# RemoteControl-v1.net
KiCad netlist of a schematic drawn in EAGLE
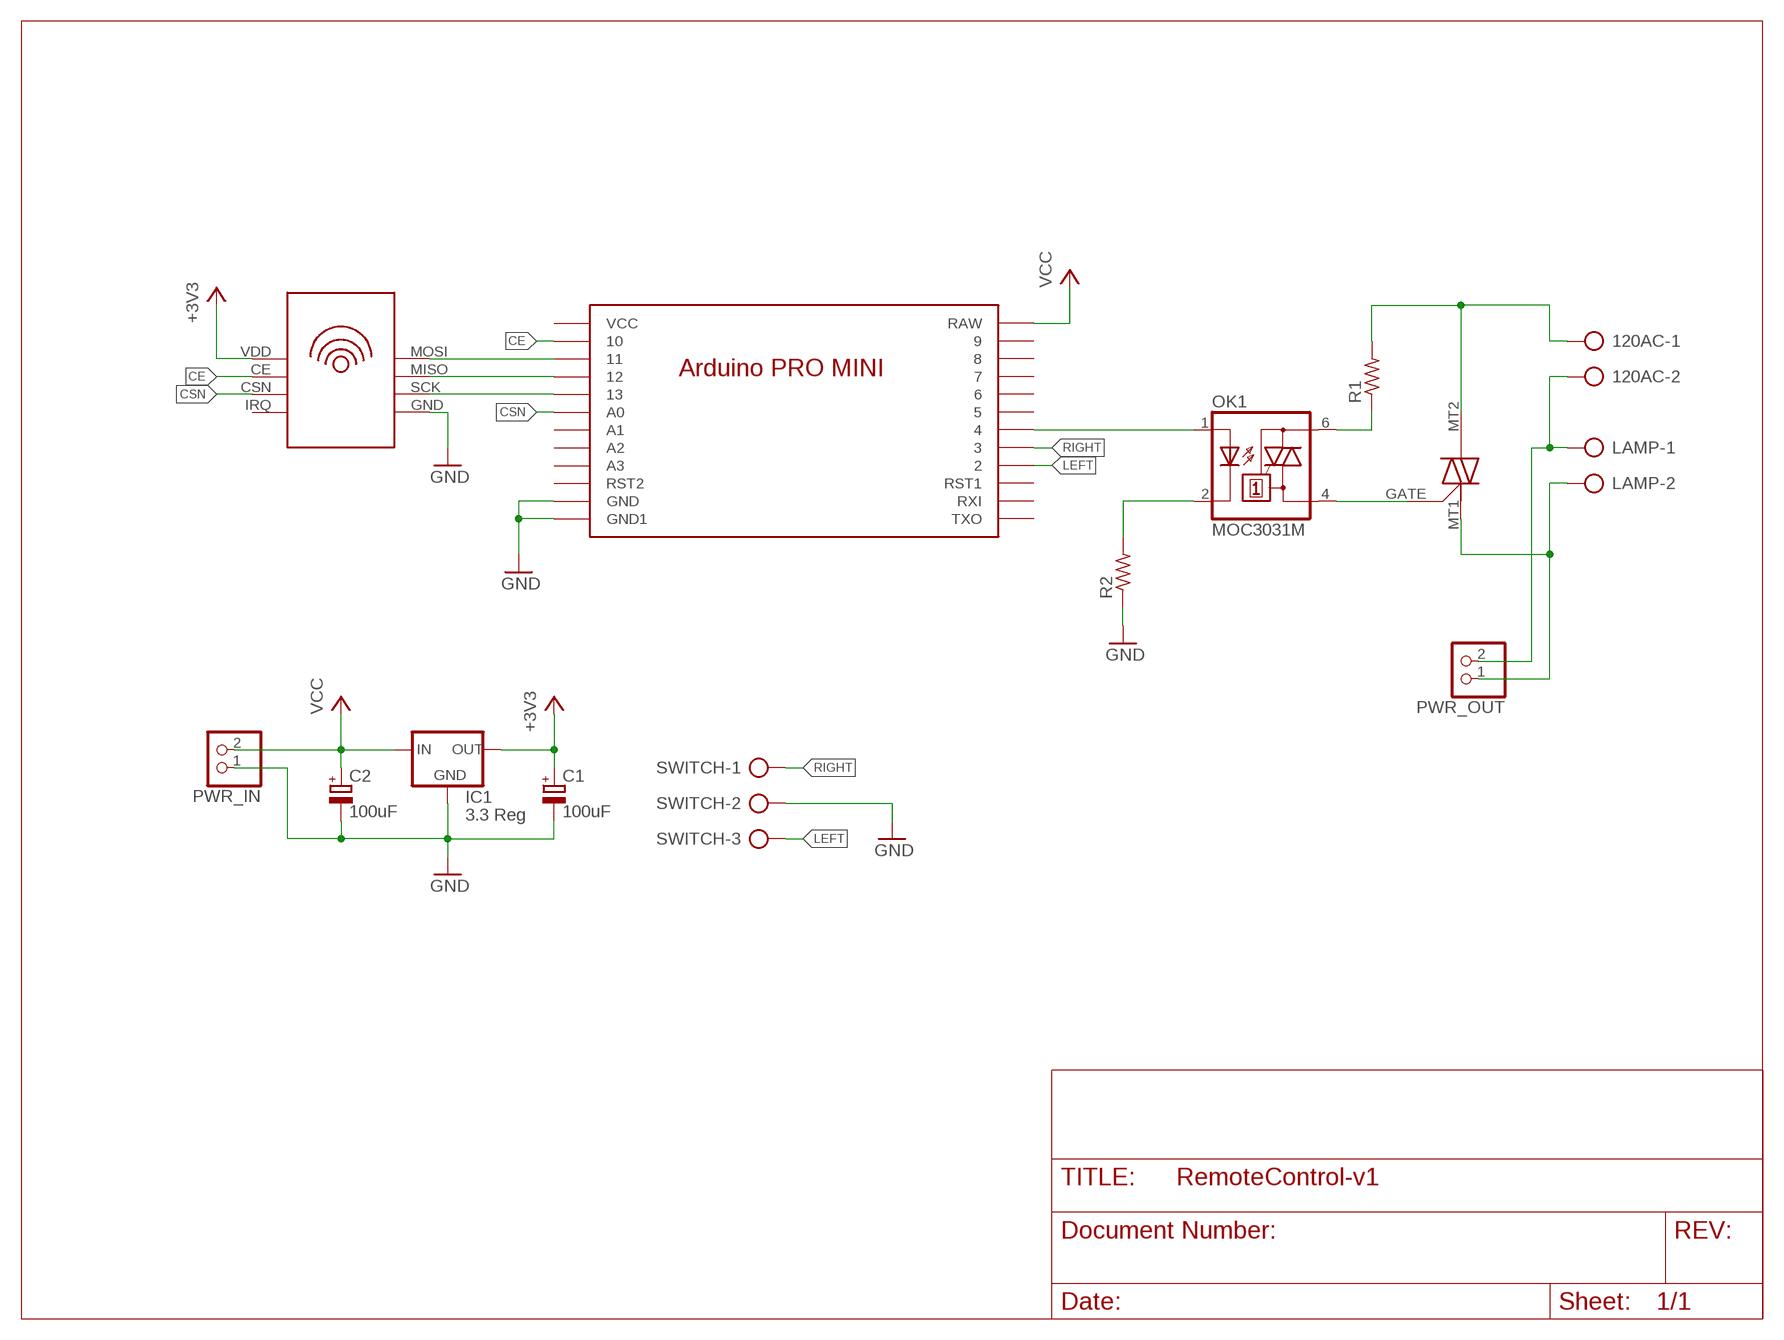
[diagram p0: schematic, sheet 1]

(export (version "E")
  (design (tool "Eeschema 10.0.6"))
  (components
    (comp (ref "120AC")
      (value "AK300/2")
      (footprint "eagle-import:AK300_2")
      (libsource (lib "eagle-import") (part "AK300/2"))
    )
    (comp (ref "C1")
      (value "100uF")
      (footprint "eagle-import:E2,5-5")
      (libsource (lib "eagle-import") (part "CPOL-EUE2.5-5"))
    )
    (comp (ref "C2")
      (value "100uF")
      (footprint "eagle-import:E2,5-5")
      (libsource (lib "eagle-import") (part "CPOL-EUE2.5-5"))
    )
    (comp (ref "IC1")
      (value "3.3 Reg")
      (footprint "eagle-import:78LXX")
      (libsource (lib "eagle-import") (part "78LXX"))
    )
    (comp (ref "LAMP")
      (value "AK300/2")
      (footprint "eagle-import:AK300_2")
      (libsource (lib "eagle-import") (part "AK300/2"))
    )
    (comp (ref "NRF24L01")
      (value "NRF24L01")
      (footprint "eagle-import:NRF24L01")
      (libsource (lib "eagle-import") (part "NRF24L01"))
    )
    (comp (ref "OK1")
      (value "MOC3031M")
      (footprint "eagle-import:DIL06")
      (fields (field (name "MF") "FAIRCHILD SEMICONDUCTOR"))
      (libsource (lib "eagle-import") (part "MOC3031M"))
    )
    (comp (ref "PWR_IN")
      (value "PINHD-1X2")
      (footprint "eagle-import:1X02")
      (libsource (lib "eagle-import") (part "PINHD-1X2"))
    )
    (comp (ref "PWR_OUT")
      (value "PINHD-1X2")
      (footprint "eagle-import:1X02")
      (libsource (lib "eagle-import") (part "PINHD-1X2"))
    )
    (comp (ref "R1")
      (value "R-US_0204/7")
      (footprint "eagle-import:0204_7")
      (libsource (lib "eagle-import") (part "R-US_0204/7"))
    )
    (comp (ref "R2")
      (value "R-US_0204/7")
      (footprint "eagle-import:0204_7")
      (libsource (lib "eagle-import") (part "R-US_0204/7"))
    )
    (comp (ref "SWITCH")
      (value "AK300/3")
      (footprint "eagle-import:AK300_3")
      (libsource (lib "eagle-import") (part "AK300/3"))
    )
    (comp (ref "U$1")
      (value "NANO")
      (footprint "eagle-import:NANO")
      (libsource (lib "eagle-import") (part "NANO"))
    )
    (comp (ref "U$2")
      (value "MAC12")
      (footprint "eagle-import:MAC12")
      (libsource (lib "eagle-import") (part "MAC12"))
    )
  )
  (nets
    (net (code "1") (name "+3V3") (class "Default")
      (node (ref "C1") (pin "+") (pinfunction "+_+") (pintype "passive"))
      (node (ref "IC1") (pin "OUT") (pinfunction "OUT_OUT") (pintype "passive"))
      (node (ref "NRF24L01") (pin "VDD") (pinfunction "VDD_VDD") (pintype "bidirectional"))
    )
    (net (code "2") (name "CE") (class "Default")
      (node (ref "NRF24L01") (pin "CE") (pinfunction "CE_CE") (pintype "bidirectional"))
      (node (ref "U$1") (pin "10") (pinfunction "10_10") (pintype "bidirectional"))
    )
    (net (code "3") (name "CSN") (class "Default")
      (node (ref "NRF24L01") (pin "CSN") (pinfunction "CSN_CSN") (pintype "bidirectional"))
      (node (ref "U$1") (pin "A0") (pinfunction "A0_A0") (pintype "bidirectional"))
    )
    (net (code "4") (name "GND") (class "Default")
      (node (ref "C1") (pin "-") (pinfunction "-_-") (pintype "passive"))
      (node (ref "C2") (pin "-") (pinfunction "-_-") (pintype "passive"))
      (node (ref "IC1") (pin "GND") (pinfunction "GND_GND") (pintype "input"))
      (node (ref "NRF24L01") (pin "GND") (pinfunction "GND_GND") (pintype "bidirectional"))
      (node (ref "PWR_IN") (pin "1") (pinfunction "1_1") (pintype "passive"))
      (node (ref "R2") (pin "1") (pinfunction "1_1") (pintype "passive"))
      (node (ref "SWITCH") (pin "2") (pinfunction "KL_2") (pintype "passive"))
      (node (ref "U$1") (pin "GND1") (pinfunction "GND_GND1") (pintype "bidirectional"))
      (node (ref "U$1") (pin "GND2") (pinfunction "GND1_GND2") (pintype "power_in"))
    )
    (net (code "5") (name "LEFT") (class "Default")
      (node (ref "SWITCH") (pin "3") (pinfunction "KL_3") (pintype "passive"))
      (node (ref "U$1") (pin "2") (pinfunction "2_2") (pintype "bidirectional"))
    )
    (net (code "6") (name "Net-(120ACA-KL)") (class "Default")
      (node (ref "120AC") (pin "1") (pinfunction "KL_1") (pintype "passive"))
      (node (ref "R1") (pin "2") (pinfunction "2_2") (pintype "passive"))
      (node (ref "U$2") (pin "MT2") (pinfunction "MT2_MT2") (pintype "bidirectional"))
    )
    (net (code "7") (name "Net-(120ACB-KL)") (class "Default")
      (node (ref "120AC") (pin "2") (pinfunction "KL_2") (pintype "passive"))
      (node (ref "LAMP") (pin "1") (pinfunction "KL_1") (pintype "passive"))
      (node (ref "PWR_OUT") (pin "2") (pinfunction "2_2") (pintype "passive"))
    )
    (net (code "8") (name "Net-(LAMPB-KL)") (class "Default")
      (node (ref "LAMP") (pin "2") (pinfunction "KL_2") (pintype "passive"))
      (node (ref "PWR_OUT") (pin "1") (pinfunction "1_1") (pintype "passive"))
      (node (ref "U$2") (pin "MT1") (pinfunction "MT1_MT1") (pintype "bidirectional"))
    )
    (net (code "9") (name "Net-(NRF24L01-PadMISO)") (class "Default")
      (node (ref "NRF24L01") (pin "MISO") (pinfunction "MISO_MISO") (pintype "bidirectional"))
      (node (ref "U$1") (pin "12") (pinfunction "12_12") (pintype "bidirectional"))
    )
    (net (code "10") (name "Net-(NRF24L01-PadMOSI)") (class "Default")
      (node (ref "NRF24L01") (pin "MOSI") (pinfunction "MOSI_MOSI") (pintype "bidirectional"))
      (node (ref "U$1") (pin "11") (pinfunction "11_11") (pintype "bidirectional"))
    )
    (net (code "11") (name "Net-(NRF24L01-PadSCK)") (class "Default")
      (node (ref "NRF24L01") (pin "SCK") (pinfunction "SCK_SCK") (pintype "bidirectional"))
      (node (ref "U$1") (pin "13") (pinfunction "13_13") (pintype "bidirectional"))
    )
    (net (code "12") (name "Net-(OK1-A)") (class "Default")
      (node (ref "OK1") (pin "1") (pinfunction "A_1") (pintype "passive"))
      (node (ref "U$1") (pin "4") (pinfunction "4_4") (pintype "bidirectional"))
    )
    (net (code "13") (name "Net-(OK1-A1)") (class "Default")
      (node (ref "OK1") (pin "4") (pinfunction "A1_4") (pintype "passive"))
      (node (ref "U$2") (pin "GATE") (pinfunction "GATE_GATE") (pintype "bidirectional"))
    )
    (net (code "14") (name "Net-(OK1-A2)") (class "Default")
      (node (ref "OK1") (pin "6") (pinfunction "A2_6") (pintype "passive"))
      (node (ref "R1") (pin "1") (pinfunction "1_1") (pintype "passive"))
    )
    (net (code "15") (name "Net-(OK1-C)") (class "Default")
      (node (ref "OK1") (pin "2") (pinfunction "C_2") (pintype "passive"))
      (node (ref "R2") (pin "2") (pinfunction "2_2") (pintype "passive"))
    )
    (net (code "16") (name "RIGHT") (class "Default")
      (node (ref "SWITCH") (pin "1") (pinfunction "KL_1") (pintype "passive"))
      (node (ref "U$1") (pin "3") (pinfunction "3_3") (pintype "bidirectional"))
    )
    (net (code "17") (name "VCC") (class "Default")
      (node (ref "C2") (pin "+") (pinfunction "+_+") (pintype "passive"))
      (node (ref "IC1") (pin "IN") (pinfunction "IN_IN") (pintype "input"))
      (node (ref "PWR_IN") (pin "2") (pinfunction "2_2") (pintype "passive"))
      (node (ref "U$1") (pin "RAW") (pinfunction "RAW_RAW") (pintype "bidirectional"))
    )
    (net (code "18") (name "unconnected-(NRF24L01-PadIRQ)") (class "Default")
      (node (ref "NRF24L01") (pin "IRQ") (pinfunction "IRQ_IRQ") (pintype "bidirectional"))
    )
    (net (code "19") (name "unconnected-(U$1-Pad5)") (class "Default")
      (node (ref "U$1") (pin "5") (pinfunction "5_5") (pintype "bidirectional"))
    )
    (net (code "20") (name "unconnected-(U$1-Pad6)") (class "Default")
      (node (ref "U$1") (pin "6") (pinfunction "6_6") (pintype "bidirectional"))
    )
    (net (code "21") (name "unconnected-(U$1-Pad7)") (class "Default")
      (node (ref "U$1") (pin "7") (pinfunction "7_7") (pintype "bidirectional"))
    )
    (net (code "22") (name "unconnected-(U$1-Pad8)") (class "Default")
      (node (ref "U$1") (pin "8") (pinfunction "8_8") (pintype "bidirectional"))
    )
    (net (code "23") (name "unconnected-(U$1-Pad9)") (class "Default")
      (node (ref "U$1") (pin "9") (pinfunction "9_9") (pintype "bidirectional"))
    )
    (net (code "24") (name "unconnected-(U$1-PadA1)") (class "Default")
      (node (ref "U$1") (pin "A1") (pinfunction "A1_A1") (pintype "bidirectional"))
    )
    (net (code "25") (name "unconnected-(U$1-PadA2)") (class "Default")
      (node (ref "U$1") (pin "A2") (pinfunction "A2_A2") (pintype "bidirectional"))
    )
    (net (code "26") (name "unconnected-(U$1-PadA3)") (class "Default")
      (node (ref "U$1") (pin "A3") (pinfunction "A3_A3") (pintype "bidirectional"))
    )
    (net (code "27") (name "unconnected-(U$1-PadRST1)") (class "Default")
      (node (ref "U$1") (pin "RST1") (pinfunction "RST1_RST1") (pintype "bidirectional"))
    )
    (net (code "28") (name "unconnected-(U$1-PadRST2)") (class "Default")
      (node (ref "U$1") (pin "RST2") (pinfunction "RST2_RST2") (pintype "bidirectional"))
    )
    (net (code "29") (name "unconnected-(U$1-PadRXI)") (class "Default")
      (node (ref "U$1") (pin "RXI") (pinfunction "RXI_RXI") (pintype "bidirectional"))
    )
    (net (code "30") (name "unconnected-(U$1-PadTXO)") (class "Default")
      (node (ref "U$1") (pin "TXO") (pinfunction "TXO_TXO") (pintype "bidirectional"))
    )
    (net (code "31") (name "unconnected-(U$1-PadVCC)") (class "Default")
      (node (ref "U$1") (pin "VCC") (pinfunction "VCC_VCC") (pintype "bidirectional"))
    )
  )
)
